# Cansat2019_1516_Container_v06.net
KiCad netlist of a schematic drawn in EAGLE
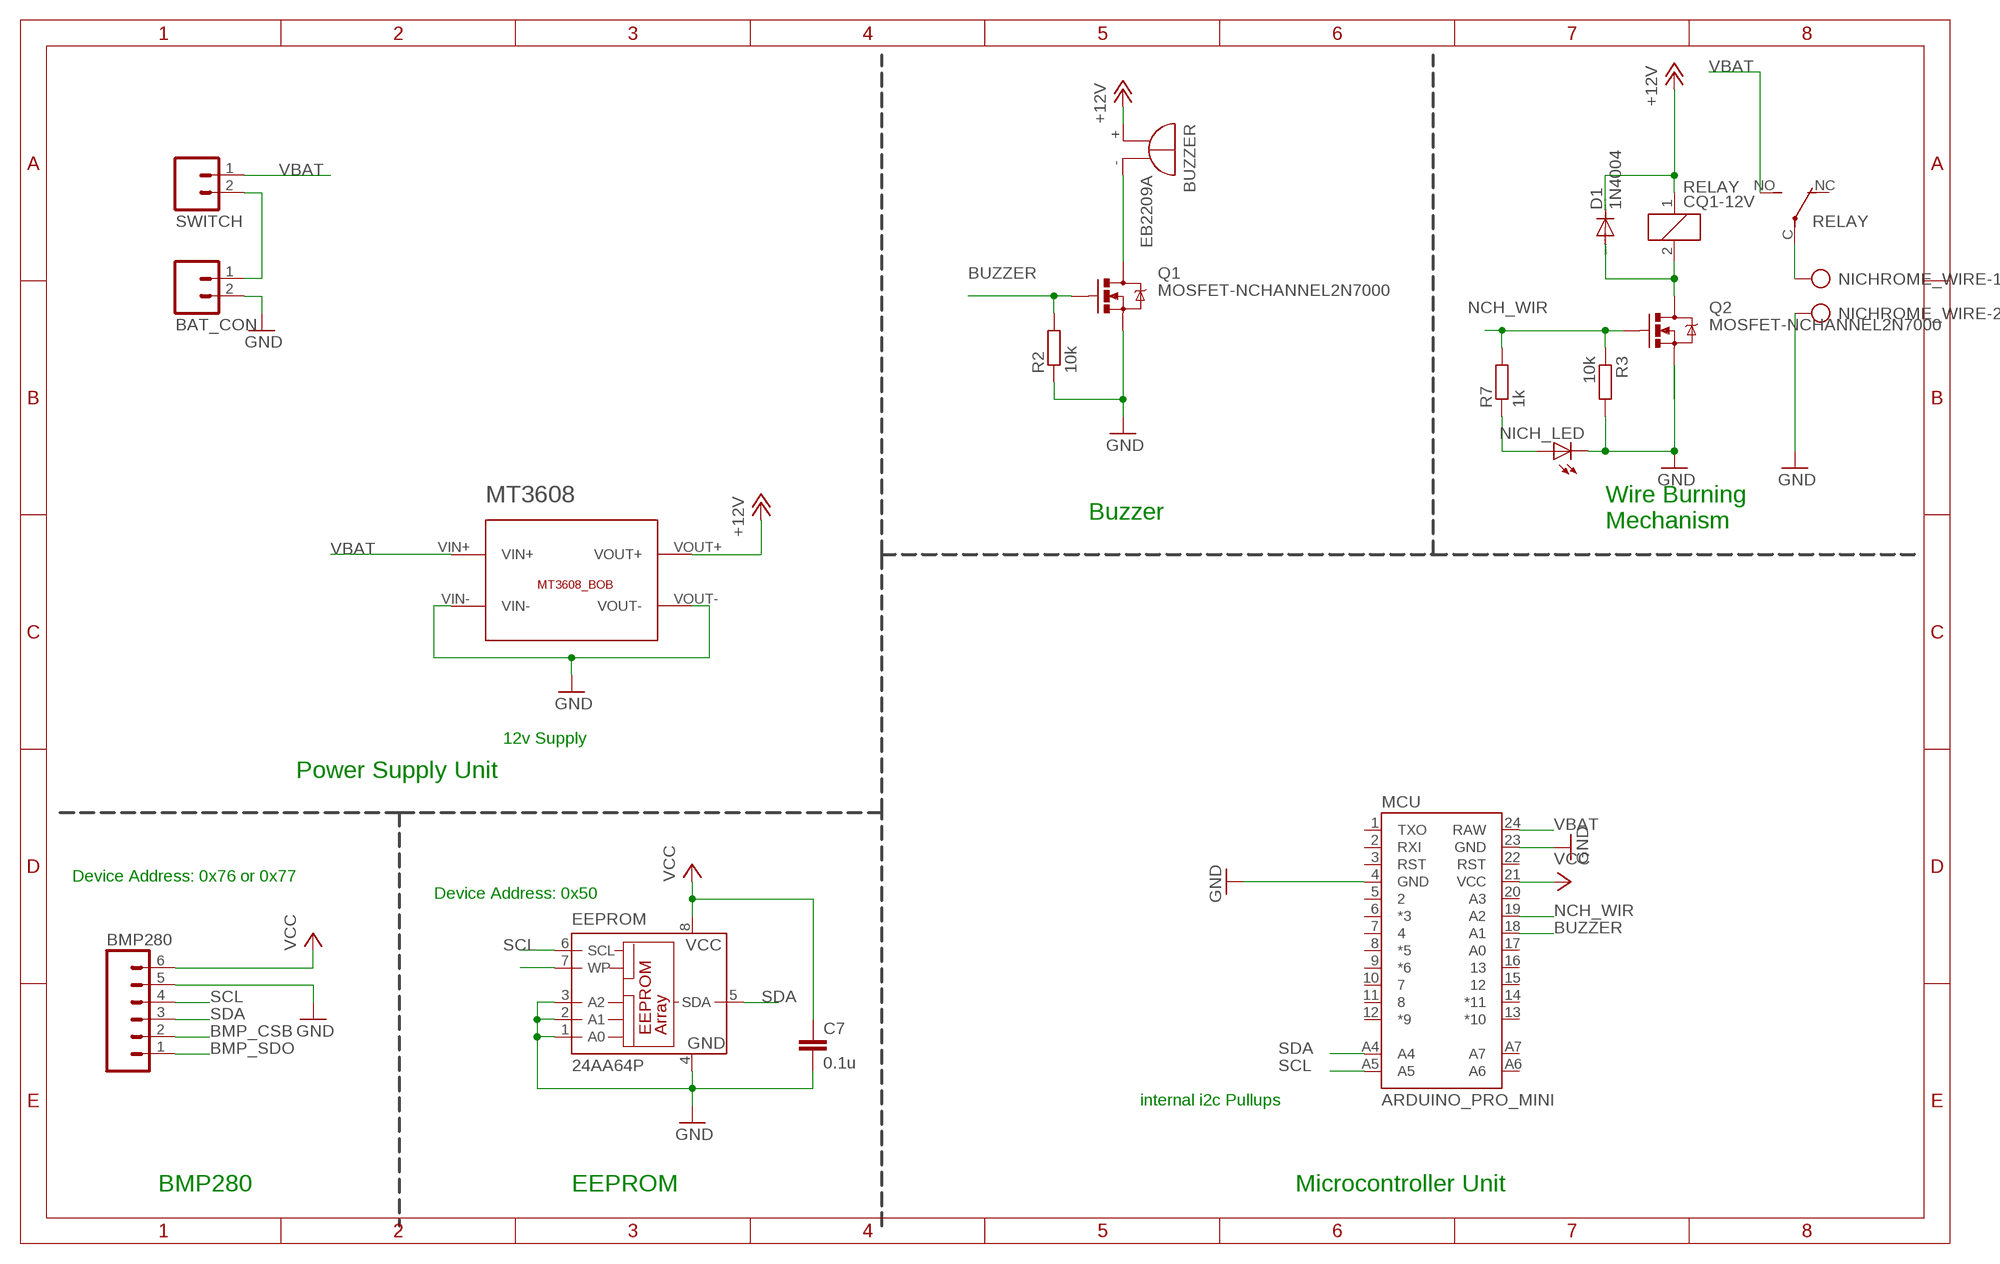
[diagram p0: schematic, sheet 1]

(export (version "E")
  (design (tool "Eeschema 10.0.6"))
  (components
    (comp (ref "BAT_CON")
      (value "M02")
      (footprint "eagle-import:02P")
      (libsource (lib "eagle-import") (part "M02"))
    )
    (comp (ref "BMP280")
      (value "M06")
      (footprint "eagle-import:06P")
      (libsource (lib "eagle-import") (part "M06"))
    )
    (comp (ref "BUZZER")
      (value "EB2209A")
      (footprint "eagle-import:EB2209A")
      (libsource (lib "eagle-import") (part "EB2209A"))
    )
    (comp (ref "C7")
      (value "0.1u")
      (footprint "eagle-import:C025-025X050")
      (libsource (lib "eagle-import") (part "C-EU025-025X050"))
    )
    (comp (ref "D1")
      (value "1N4004")
      (footprint "eagle-import:DO41-10")
      (libsource (lib "eagle-import") (part "1N4004"))
    )
    (comp (ref "EEPROM")
      (value "24AA64P")
      (footprint "eagle-import:DIL8")
      (fields (field (name "MF") "MICROCHIP") (field (name "MPN") "24AA64-I/P"))
      (libsource (lib "eagle-import") (part "24PAA64"))
    )
    (comp (ref "MCU")
      (value "ARDUINO_PRO_MINI")
      (footprint "eagle-import:ARDUINO_PRO_MINI")
      (libsource (lib "eagle-import") (part "ARDUINO_PRO_MINI"))
    )
    (comp (ref "MT3608")
      (value "MT3608_BOB")
      (footprint "eagle-import:MT3608_BOB")
      (libsource (lib "eagle-import") (part "MT3608_BOB"))
    )
    (comp (ref "NICHROME_WIRE")
      (value "AK500/2-H")
      (footprint "eagle-import:AK500_2-H")
      (libsource (lib "eagle-import") (part "AK500/2-H"))
    )
    (comp (ref "NICH_LED")
      (value "LED3MM")
      (footprint "eagle-import:LED3MM")
      (libsource (lib "eagle-import") (part "LED3MM"))
    )
    (comp (ref "Q1")
      (value "MOSFET-NCHANNEL2N7000")
      (footprint "eagle-import:TO-92")
      (libsource (lib "eagle-import") (part "MOSFET-NCHANNEL2N7000"))
    )
    (comp (ref "Q2")
      (value "MOSFET-NCHANNEL2N7000")
      (footprint "eagle-import:TO-92")
      (libsource (lib "eagle-import") (part "MOSFET-NCHANNEL2N7000"))
    )
    (comp (ref "R2")
      (value "10k")
      (footprint "eagle-import:0204_7")
      (libsource (lib "eagle-import") (part "R-EU_0204/7"))
    )
    (comp (ref "R3")
      (value "10k")
      (footprint "eagle-import:0204_7")
      (libsource (lib "eagle-import") (part "R-EU_0204/7"))
    )
    (comp (ref "R7")
      (value "1k")
      (footprint "eagle-import:0204_7")
      (libsource (lib "eagle-import") (part "R-EU_0204/7"))
    )
    (comp (ref "RELAY")
      (value "CQ1-12V")
      (footprint "eagle-import:CQ1")
      (libsource (lib "eagle-import") (part "CQ1-12V"))
    )
    (comp (ref "SWITCH")
      (value "M02")
      (footprint "eagle-import:02P")
      (libsource (lib "eagle-import") (part "M02"))
    )
  )
  (nets
    (net (code "1") (name "+12V") (class "Default")
      (node (ref "BUZZER") (pin "+") (pinfunction "+_+") (pintype "passive"))
      (node (ref "D1") (pin "C") (pinfunction "C_C") (pintype "passive"))
      (node (ref "MT3608") (pin "VOUT+") (pinfunction "VOUT+_VOUT+") (pintype "bidirectional"))
      (node (ref "RELAY") (pin "1") (pinfunction "1_1") (pintype "passive"))
    )
    (net (code "2") (name "/BMP_CSB") (class "Default")
      (node (ref "BMP280") (pin "2") (pinfunction "2_2") (pintype "passive"))
    )
    (net (code "3") (name "/BMP_SDO") (class "Default")
      (node (ref "BMP280") (pin "1") (pinfunction "1_1") (pintype "passive"))
    )
    (net (code "4") (name "/BUZZER") (class "Default")
      (node (ref "MCU") (pin "18") (pinfunction "A1_18") (pintype "bidirectional"))
      (node (ref "Q1") (pin "2") (pinfunction "G_2") (pintype "passive"))
      (node (ref "R2") (pin "2") (pinfunction "2_2") (pintype "passive"))
    )
    (net (code "5") (name "/NCH_WIR") (class "Default")
      (node (ref "MCU") (pin "19") (pinfunction "A2_19") (pintype "bidirectional"))
      (node (ref "Q2") (pin "2") (pinfunction "G_2") (pintype "passive"))
      (node (ref "R3") (pin "1") (pinfunction "1_1") (pintype "passive"))
      (node (ref "R7") (pin "2") (pinfunction "2_2") (pintype "passive"))
    )
    (net (code "6") (name "/SCL") (class "Default")
      (node (ref "BMP280") (pin "4") (pinfunction "4_4") (pintype "passive"))
      (node (ref "EEPROM") (pin "6") (pinfunction "SCL_6") (pintype "input"))
      (node (ref "MCU") (pin "A5") (pinfunction "A5_A5") (pintype "bidirectional"))
    )
    (net (code "7") (name "/SDA") (class "Default")
      (node (ref "BMP280") (pin "3") (pinfunction "3_3") (pintype "passive"))
      (node (ref "EEPROM") (pin "5") (pinfunction "SDA_5") (pintype "bidirectional"))
      (node (ref "MCU") (pin "A4") (pinfunction "A4_A4") (pintype "bidirectional"))
    )
    (net (code "8") (name "/VBAT") (class "Default")
      (node (ref "MCU") (pin "24") (pinfunction "RAW_24") (pintype "bidirectional"))
      (node (ref "MT3608") (pin "VIN+") (pinfunction "VIN+_VIN+") (pintype "bidirectional"))
      (node (ref "RELAY") (pin "NO") (pinfunction "S_NO") (pintype "passive"))
      (node (ref "SWITCH") (pin "1") (pinfunction "1_1") (pintype "passive"))
    )
    (net (code "9") (name "GND") (class "Default")
      (node (ref "BAT_CON") (pin "2") (pinfunction "2_2") (pintype "passive"))
      (node (ref "BMP280") (pin "5") (pinfunction "5_5") (pintype "passive"))
      (node (ref "C7") (pin "2") (pinfunction "2_2") (pintype "passive"))
      (node (ref "EEPROM") (pin "1") (pinfunction "A0_1") (pintype "input"))
      (node (ref "EEPROM") (pin "2") (pinfunction "A1_2") (pintype "input"))
      (node (ref "EEPROM") (pin "3") (pinfunction "A2_3") (pintype "input"))
      (node (ref "EEPROM") (pin "4") (pinfunction "GND_4") (pintype "power_in"))
      (node (ref "MCU") (pin "23") (pinfunction "GND_23") (pintype "bidirectional"))
      (node (ref "MCU") (pin "4") (pinfunction "GND_4") (pintype "bidirectional"))
      (node (ref "MT3608") (pin "VIN-") (pinfunction "VIN-_VIN-") (pintype "bidirectional"))
      (node (ref "MT3608") (pin "VOUT-") (pinfunction "VOUT-_VOUT-") (pintype "bidirectional"))
      (node (ref "NICHROME_WIRE") (pin "2") (pinfunction "KL_2") (pintype "passive"))
      (node (ref "NICH_LED") (pin "K") (pinfunction "C_K") (pintype "passive"))
      (node (ref "Q1") (pin "1") (pinfunction "S_1") (pintype "passive"))
      (node (ref "Q2") (pin "1") (pinfunction "S_1") (pintype "passive"))
      (node (ref "R2") (pin "1") (pinfunction "1_1") (pintype "passive"))
      (node (ref "R3") (pin "2") (pinfunction "2_2") (pintype "passive"))
    )
    (net (code "10") (name "Net-(BAT_CON-Pad1)") (class "Default")
      (node (ref "BAT_CON") (pin "1") (pinfunction "1_1") (pintype "passive"))
      (node (ref "SWITCH") (pin "2") (pinfunction "2_2") (pintype "passive"))
    )
    (net (code "11") (name "Net-(NICHROME_WIREA-KL)") (class "Default")
      (node (ref "NICHROME_WIRE") (pin "1") (pinfunction "KL_1") (pintype "passive"))
      (node (ref "RELAY") (pin "C") (pinfunction "P_C") (pintype "passive"))
    )
    (net (code "12") (name "Net-(NICH_LED-PadA)") (class "Default")
      (node (ref "NICH_LED") (pin "A") (pinfunction "A_A") (pintype "passive"))
      (node (ref "R7") (pin "1") (pinfunction "1_1") (pintype "passive"))
    )
    (net (code "13") (name "Net-(Q1-D)") (class "Default")
      (node (ref "BUZZER") (pin "-") (pinfunction "-_-") (pintype "passive"))
      (node (ref "Q1") (pin "3") (pinfunction "D_3") (pintype "passive"))
    )
    (net (code "14") (name "Net-(Q2-D)") (class "Default")
      (node (ref "D1") (pin "A") (pinfunction "A_A") (pintype "passive"))
      (node (ref "Q2") (pin "3") (pinfunction "D_3") (pintype "passive"))
      (node (ref "RELAY") (pin "2") (pinfunction "2_2") (pintype "passive"))
    )
    (net (code "15") (name "VCC") (class "Default")
      (node (ref "BMP280") (pin "6") (pinfunction "6_6") (pintype "passive"))
      (node (ref "C7") (pin "1") (pinfunction "1_1") (pintype "passive"))
      (node (ref "EEPROM") (pin "8") (pinfunction "VCC_8") (pintype "power_in"))
      (node (ref "MCU") (pin "21") (pinfunction "VCC_21") (pintype "bidirectional"))
    )
    (net (code "16") (name "unconnected-(EEPROM-WP-Pad7)") (class "Default")
      (node (ref "EEPROM") (pin "7") (pinfunction "WP_7") (pintype "input"))
    )
    (net (code "17") (name "unconnected-(MCU-*3-Pad6)") (class "Default")
      (node (ref "MCU") (pin "6") (pinfunction "*3_6") (pintype "bidirectional"))
    )
    (net (code "18") (name "unconnected-(MCU-*5-Pad8)") (class "Default")
      (node (ref "MCU") (pin "8") (pinfunction "*5_8") (pintype "bidirectional"))
    )
    (net (code "19") (name "unconnected-(MCU-*6-Pad9)") (class "Default")
      (node (ref "MCU") (pin "9") (pinfunction "*6_9") (pintype "bidirectional"))
    )
    (net (code "20") (name "unconnected-(MCU-*9-Pad12)") (class "Default")
      (node (ref "MCU") (pin "12") (pinfunction "*9_12") (pintype "bidirectional"))
    )
    (net (code "21") (name "unconnected-(MCU-*10-Pad13)") (class "Default")
      (node (ref "MCU") (pin "13") (pinfunction "*10_13") (pintype "bidirectional"))
    )
    (net (code "22") (name "unconnected-(MCU-*11-Pad14)") (class "Default")
      (node (ref "MCU") (pin "14") (pinfunction "*11_14") (pintype "bidirectional"))
    )
    (net (code "23") (name "unconnected-(MCU-2-Pad5)") (class "Default")
      (node (ref "MCU") (pin "5") (pinfunction "2_5") (pintype "bidirectional"))
    )
    (net (code "24") (name "unconnected-(MCU-4-Pad7)") (class "Default")
      (node (ref "MCU") (pin "7") (pinfunction "4_7") (pintype "bidirectional"))
    )
    (net (code "25") (name "unconnected-(MCU-7-Pad10)") (class "Default")
      (node (ref "MCU") (pin "10") (pinfunction "7_10") (pintype "bidirectional"))
    )
    (net (code "26") (name "unconnected-(MCU-8-Pad11)") (class "Default")
      (node (ref "MCU") (pin "11") (pinfunction "8_11") (pintype "bidirectional"))
    )
    (net (code "27") (name "unconnected-(MCU-12-Pad15)") (class "Default")
      (node (ref "MCU") (pin "15") (pinfunction "12_15") (pintype "bidirectional"))
    )
    (net (code "28") (name "unconnected-(MCU-13-Pad16)") (class "Default")
      (node (ref "MCU") (pin "16") (pinfunction "13_16") (pintype "bidirectional"))
    )
    (net (code "29") (name "unconnected-(MCU-A0-Pad17)") (class "Default")
      (node (ref "MCU") (pin "17") (pinfunction "A0_17") (pintype "bidirectional"))
    )
    (net (code "30") (name "unconnected-(MCU-A3-Pad20)") (class "Default")
      (node (ref "MCU") (pin "20") (pinfunction "A3_20") (pintype "bidirectional"))
    )
    (net (code "31") (name "unconnected-(MCU-PadA6)") (class "Default")
      (node (ref "MCU") (pin "A6") (pinfunction "A6_A6") (pintype "bidirectional"))
    )
    (net (code "32") (name "unconnected-(MCU-PadA7)") (class "Default")
      (node (ref "MCU") (pin "A7") (pinfunction "A7_A7") (pintype "bidirectional"))
    )
    (net (code "33") (name "unconnected-(MCU-RST-Pad3)") (class "Default")
      (node (ref "MCU") (pin "3") (pinfunction "RST_3") (pintype "bidirectional"))
    )
    (net (code "34") (name "unconnected-(MCU-RST-Pad22)") (class "Default")
      (node (ref "MCU") (pin "22") (pinfunction "RST_22") (pintype "bidirectional"))
    )
    (net (code "35") (name "unconnected-(MCU-RXI-Pad2)") (class "Default")
      (node (ref "MCU") (pin "2") (pinfunction "RXI_2") (pintype "bidirectional"))
    )
    (net (code "36") (name "unconnected-(MCU-TXO-Pad1)") (class "Default")
      (node (ref "MCU") (pin "1") (pinfunction "TXO_1") (pintype "bidirectional"))
    )
    (net (code "37") (name "unconnected-(RELAYB-O-PadNC)") (class "Default")
      (node (ref "RELAY") (pin "NC") (pinfunction "O_NC") (pintype "passive"))
    )
  )
)
